# design.net
KiCad netlist of a schematic drawn in Altium Designer
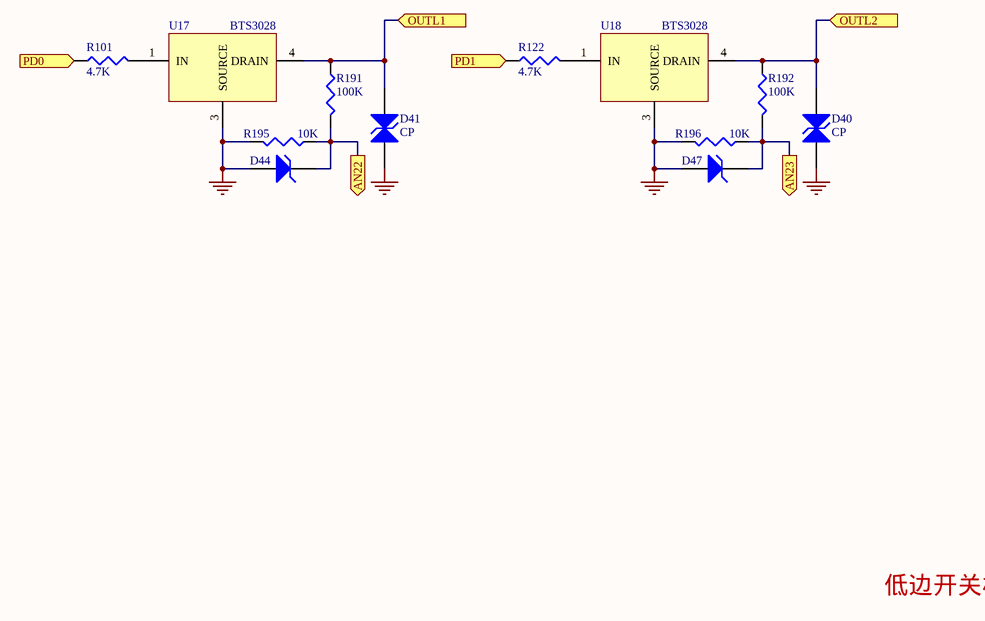
[diagram p0: 低边开关模块.SchDoc]

(export (version "E")
  (design (tool "Eeschema 10.0.6"))
  (components
    (comp (ref "D40") (value "CP") (footprint "E52") (libsource (lib "整车控制器") (part "CP")))
    (comp (ref "D41") (value "CP") (footprint "E52") (libsource (lib "整车控制器") (part "CP")))
    (comp (ref "D44")
      (value "D Zener")
      (footprint "0805")
      (description "Zener Diode")
      (fields (field (name "PUBLISHER") "Altium Limited"))
      (libsource (lib "Miscellaneous Devices") (part "D Zener"))
    )
    (comp (ref "D47")
      (value "D Zener")
      (footprint "0805")
      (description "Zener Diode")
      (fields (field (name "PUBLISHER") "Altium Limited"))
      (libsource (lib "Miscellaneous Devices") (part "D Zener"))
    )
    (comp (ref "R101")
      (value "4.7K")
      (footprint "RES1206")
      (description "Resistor")
      (fields (field (name "Comment") "Res3") (field (name "PUBLISHER") "Altium Limited"))
      (libsource (lib "Miscellaneous Devices") (part "Res3"))
    )
    (comp (ref "R122")
      (value "4.7K")
      (footprint "RES1206")
      (description "Resistor")
      (fields (field (name "Comment") "Res3") (field (name "PUBLISHER") "Altium Limited"))
      (libsource (lib "Miscellaneous Devices") (part "Res3"))
    )
    (comp (ref "R191")
      (value "100K")
      (footprint "0603-L")
      (description "Resistor")
      (fields (field (name "Comment") "Res3") (field (name "PUBLISHER") "Altium Limited"))
      (libsource (lib "Miscellaneous Devices") (part "Res3"))
    )
    (comp (ref "R192")
      (value "100K")
      (footprint "0603-L")
      (description "Resistor")
      (fields (field (name "Comment") "Res3") (field (name "PUBLISHER") "Altium Limited"))
      (libsource (lib "Miscellaneous Devices") (part "Res3"))
    )
    (comp (ref "R195")
      (value "10K")
      (footprint "0603-L")
      (description "Resistor")
      (fields (field (name "Comment") "Res3") (field (name "PUBLISHER") "Altium Limited"))
      (libsource (lib "Miscellaneous Devices") (part "Res3"))
    )
    (comp (ref "R196")
      (value "10K")
      (footprint "0603-L")
      (description "Resistor")
      (fields (field (name "Comment") "Res3") (field (name "PUBLISHER") "Altium Limited"))
      (libsource (lib "Miscellaneous Devices") (part "Res3"))
    )
    (comp (ref "U17")
      (value "BTS3028")
      (footprint "BTS3028")
      (description "Smart Low Side Power Switch")
      (libsource (lib "BMS") (part "BTS3028"))
    )
    (comp (ref "U18")
      (value "BTS3028")
      (footprint "BTS3028")
      (description "Smart Low Side Power Switch")
      (libsource (lib "BMS") (part "BTS3028"))
    )
  )
  (nets
    (net (code "1") (name "/AN22") (class "Default")
      (node (ref "D44") (pin "2") (pinfunction "K_2") (pintype "passive"))
      (node (ref "R191") (pin "2") (pinfunction "2_2") (pintype "passive"))
      (node (ref "R195") (pin "1") (pinfunction "1_1") (pintype "passive"))
    )
    (net (code "2") (name "/AN23") (class "Default")
      (node (ref "D47") (pin "2") (pinfunction "K_2") (pintype "passive"))
      (node (ref "R192") (pin "2") (pinfunction "2_2") (pintype "passive"))
      (node (ref "R196") (pin "1") (pinfunction "1_1") (pintype "passive"))
    )
    (net (code "3") (name "/OUTL1") (class "Default")
      (node (ref "D41") (pin "1") (pinfunction "A1_1") (pintype "passive"))
      (node (ref "R191") (pin "1") (pinfunction "1_1") (pintype "passive"))
      (node (ref "U17") (pin "4") (pinfunction "DRAIN_4") (pintype "passive"))
    )
    (net (code "4") (name "/OUTL2") (class "Default")
      (node (ref "D40") (pin "1") (pinfunction "A1_1") (pintype "passive"))
      (node (ref "R192") (pin "1") (pinfunction "1_1") (pintype "passive"))
      (node (ref "U18") (pin "4") (pinfunction "DRAIN_4") (pintype "passive"))
    )
    (net (code "5") (name "/PD0") (class "Default")
      (node (ref "R101") (pin "1") (pinfunction "1_1") (pintype "passive"))
    )
    (net (code "6") (name "/PD1") (class "Default")
      (node (ref "R122") (pin "1") (pinfunction "1_1") (pintype "passive"))
    )
    (net (code "7") (name "GND") (class "Default")
      (node (ref "D40") (pin "2") (pinfunction "A2_2") (pintype "passive"))
      (node (ref "D41") (pin "2") (pinfunction "A2_2") (pintype "passive"))
      (node (ref "D44") (pin "1") (pinfunction "A_1") (pintype "passive"))
      (node (ref "D47") (pin "1") (pinfunction "A_1") (pintype "passive"))
      (node (ref "R195") (pin "2") (pinfunction "2_2") (pintype "passive"))
      (node (ref "R196") (pin "2") (pinfunction "2_2") (pintype "passive"))
      (node (ref "U17") (pin "3") (pinfunction "SOURCE_3") (pintype "passive"))
      (node (ref "U18") (pin "3") (pinfunction "SOURCE_3") (pintype "passive"))
    )
    (net (code "8") (name "Net-(U17-IN)") (class "Default")
      (node (ref "R101") (pin "2") (pinfunction "2_2") (pintype "passive"))
      (node (ref "U17") (pin "1") (pinfunction "IN_1") (pintype "passive"))
    )
    (net (code "9") (name "Net-(U18-IN)") (class "Default")
      (node (ref "R122") (pin "2") (pinfunction "2_2") (pintype "passive"))
      (node (ref "U18") (pin "1") (pinfunction "IN_1") (pintype "passive"))
    )
  )
)
